# DCDC_Traco.net
KiCad netlist of a schematic drawn in Altium Designer
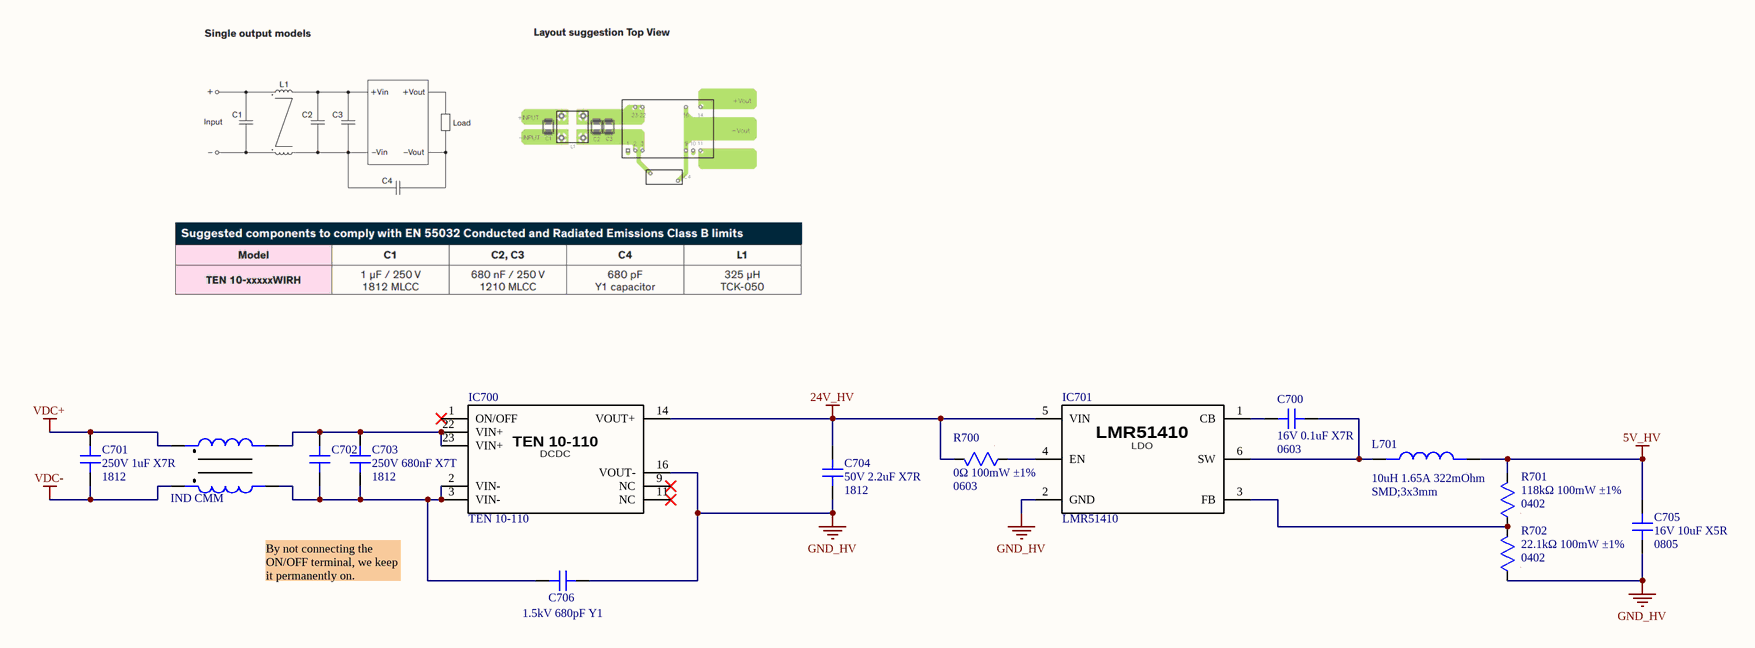
[diagram p0: DCDC_Traco.SchDoc]

(export (version "E")
  (design (tool "Eeschema 10.0.6"))
  (components
    (comp (ref "C700")
      (value "16V 0.1uF X7R")
      (footprint "CAP SMD 0603")
      (description "Condensadores de cerámica multicapa (MLCC- SMD/SMT) WCAP-CSGP 0.1uF 0603 10% 16V MLCC")
      (fields
        (field (name "PACKAGE") "0603")
        (field (name "MPN") "885012206046")
        (field (name "MANUFACTURER") "Wurth Elektronik")
      )
      (libsource (lib "eUSR_Database") (part "CAP non polarized"))
    )
    (comp (ref "C701")
      (value "250V 1uF X7R")
      (footprint "CAP SMD 1812")
      (description "Condensadores de cerámica multicapa (MLCC- SMD/SMT) 250V 1uF X7R 1812 10 %")
      (fields
        (field (name "PACKAGE") "1812")
        (field (name "MPN") "1812VC105KAT2A")
        (field (name "MANUFACTURER") "KYOCERA AVX")
      )
      (libsource (lib "eUSR_Database") (part "CAP non polarized"))
    )
    (comp (ref "C702")
      (value "CAP non polarized")
      (footprint "CAP SMD 1812")
      (description "Condensadores de cerámica multicapa (MLCC- SMD/SMT) 1812 250V 0.68uF X7T 20% T: 1.6mm")
      (fields (field (name "MPN") "C4532X7T2E684M160KA") (field (name "MANUFACTURER") "TDK"))
      (libsource (lib "eUSR_Database") (part "CAP non polarized"))
    )
    (comp (ref "C703")
      (value "250V 680nF X7T")
      (footprint "CAP SMD 1812")
      (description "Condensadores de cerámica multicapa (MLCC- SMD/SMT) 1812 250V 0.68uF X7T 20% T: 1.6mm")
      (fields
        (field (name "PACKAGE") "1812")
        (field (name "MPN") "C4532X7T2E684M160KA")
        (field (name "MANUFACTURER") "TDK")
      )
      (libsource (lib "eUSR_Database") (part "CAP non polarized"))
    )
    (comp (ref "C704")
      (value "50V 2.2uF X7R")
      (footprint "CAP SMD 1812")
      (description "Condensadores de cerámica multicapa (MLCC- SMD/SMT) WCAP-CSGP 2.2uF 1812 10% 50V MLCC")
      (fields
        (field (name "PACKAGE") "1812")
        (field (name "MPN") "885012210032")
        (field (name "MANUFACTURER") "Wurth Elektronik")
      )
      (libsource (lib "eUSR_Database") (part "CAP non polarized"))
    )
    (comp (ref "C705")
      (value "16V 10uF X5R")
      (footprint "CAP SMD 0805")
      (description "Condensadores de cerámica multicapa (MLCC- SMD/SMT) WCAP-CSGP 10uF 0805 20% 16V MLCC")
      (fields
        (field (name "PACKAGE") "0805")
        (field (name "MPN") "885012107014")
        (field (name "MANUFACTURER") "Wurth Elektronik")
      )
      (libsource (lib "eUSR_Database") (part "CAP non polarized"))
    )
    (comp (ref "C706")
      (value "1.5kV 680pF Y1")
      (footprint "CAP_15Px12.5H")
      (description "Condensadores de seguridad 500volts 680pF 20% LS=15mm")
      (fields (field (name "MPN") "P295BE681M500A") (field (name "MANUFACTURER") "KEMET"))
      (libsource (lib "eUSR_Database") (part "CAP non polarized"))
    )
    (comp (ref "IC700")
      (value "TEN 10-110")
      (footprint "TEN 10-110")
      (fields (field (name "MPN") "TEN 10-11015WIRH") (field (name "MANUFACTURER") "TRACO Power"))
      (libsource (lib "eUSR_Database") (part "TEN 10-110"))
    )
    (comp (ref "IC701")
      (value "LMR51410")
      (footprint "SOT-23-6")
      (description "Reguladores de tensión de conmutación SIMPLE SWITCHER 4V t o 42V 1A synchronou")
      (fields (field (name "MPN") "LMR51410YFDBVR") (field (name "MANUFACTURER") "Texas Instruments"))
      (libsource (lib "eUSR_Database") (part "LMR51410"))
    )
    (comp (ref "L700")
      (value "IND CMM")
      (footprint "IND_CMM_THT_11x11mm")
      (description "Cebadores / filtros de modo común Filter Component")
      (fields (field (name "MPN") "TCK-050") (field (name "MANUFACTURER") "TRACO Power"))
      (libsource (lib "eUSR_Database") (part "IND CMM"))
    )
    (comp (ref "L701")
      (value "10uH 1.65A 322mOhm")
      (footprint "IND SMD 3x3")
      (description "Inductores de potencia (SMD) WE-MAPI 10uH 1.2A DCR=322mOhms AEC-Q200")
      (fields
        (field (name "PACKAGE") "SMD;3x3mm")
        (field (name "MPN") "74438336100")
        (field (name "MANUFACTURER") "Wurth Elektronik")
      )
      (libsource (lib "eUSR_Database") (part "IND"))
    )
    (comp (ref "R700")
      (value "0Ω 100mW ±1%")
      (footprint "RES SMD 0603")
      (description "Resistores de película gruesa - SMD WRIS-RSKS <0.05 Ohms 0.1 W Jumper 0603 AEC-Q200")
      (fields
        (field (name "PACKAGE") "0603")
        (field (name "MPN") "5,60112116e+11")
        (field (name "MANUFACTURER") "Wurth Elektronik")
      )
      (libsource (lib "eUSR_Database") (part "RES"))
    )
    (comp (ref "R701")
      (value "118kΩ 100mW ±1%")
      (footprint "RES SMD 0402")
      (description "Resistores de película gruesa - SMD WRIS-RSKS 118 kOhms 1 % 0.1 W 0402 AEC-Q200")
      (fields
        (field (name "PACKAGE") "0402")
        (field (name "MPN") "560112110142")
        (field (name "MANUFACTURER") "Wurth Elektronik")
      )
      (libsource (lib "eUSR_Database") (part "RES"))
    )
    (comp (ref "R702")
      (value "22.1kΩ 100mW ±1%")
      (footprint "RES SMD 0402")
      (description "Resistores de película gruesa - SMD WRIS-RSKS 22.1 kOhms 1 % 0.1 W 0402 AEC-Q200")
      (fields
        (field (name "PACKAGE") "0402")
        (field (name "MPN") "560112110099")
        (field (name "MANUFACTURER") "Wurth Elektronik")
      )
      (libsource (lib "eUSR_Database") (part "RES"))
    )
  )
  (nets
    (net (code "1") (name "5V_HV") (class "Default")
      (node (ref "C705") (pin "1") (pinfunction "1_1") (pintype "passive"))
      (node (ref "L701") (pin "2") (pinfunction "2_2") (pintype "passive"))
      (node (ref "R701") (pin "2") (pinfunction "2_2") (pintype "passive"))
    )
    (net (code "2") (name "24V_HV") (class "Default")
      (node (ref "C704") (pin "1") (pinfunction "1_1") (pintype "passive"))
      (node (ref "IC700") (pin "14") (pinfunction "VOUT+_14") (pintype "passive"))
      (node (ref "IC701") (pin "5") (pinfunction "VIN_5") (pintype "passive"))
      (node (ref "R700") (pin "2") (pinfunction "2_2") (pintype "passive"))
    )
    (net (code "3") (name "GND_HV") (class "Default")
      (node (ref "C704") (pin "2") (pinfunction "2_2") (pintype "passive"))
      (node (ref "C705") (pin "2") (pinfunction "2_2") (pintype "passive"))
      (node (ref "C706") (pin "2") (pinfunction "2_2") (pintype "passive"))
      (node (ref "IC700") (pin "16") (pinfunction "VOUT-_16") (pintype "passive"))
      (node (ref "IC701") (pin "2") (pinfunction "GND_2") (pintype "passive"))
      (node (ref "R702") (pin "1") (pinfunction "1_1") (pintype "passive"))
    )
    (net (code "4") (name "Net-(C702-Pad1)") (class "Default")
      (node (ref "C702") (pin "1") (pinfunction "1_1") (pintype "passive"))
      (node (ref "C703") (pin "1") (pinfunction "1_1") (pintype "passive"))
      (node (ref "IC700") (pin "22") (pinfunction "VIN+_22") (pintype "passive"))
      (node (ref "IC700") (pin "23") (pinfunction "VIN+_23") (pintype "passive"))
      (node (ref "L700") (pin "2") (pinfunction "2_2") (pintype "passive"))
    )
    (net (code "5") (name "Net-(C702-Pad2)") (class "Default")
      (node (ref "C702") (pin "2") (pinfunction "2_2") (pintype "passive"))
      (node (ref "C703") (pin "2") (pinfunction "2_2") (pintype "passive"))
      (node (ref "C706") (pin "1") (pinfunction "1_1") (pintype "passive"))
      (node (ref "IC700") (pin "2") (pinfunction "VIN-_2") (pintype "passive"))
      (node (ref "IC700") (pin "3") (pinfunction "VIN-_3") (pintype "passive"))
      (node (ref "L700") (pin "3") (pinfunction "3_3") (pintype "passive"))
    )
    (net (code "6") (name "Net-(IC701-CB)") (class "Default")
      (node (ref "C700") (pin "1") (pinfunction "1_1") (pintype "passive"))
      (node (ref "IC701") (pin "1") (pinfunction "CB_1") (pintype "passive"))
    )
    (net (code "7") (name "Net-(IC701-EN)") (class "Default")
      (node (ref "IC701") (pin "4") (pinfunction "EN_4") (pintype "passive"))
      (node (ref "R700") (pin "1") (pinfunction "1_1") (pintype "passive"))
    )
    (net (code "8") (name "Net-(IC701-FB)") (class "Default")
      (node (ref "IC701") (pin "3") (pinfunction "FB_3") (pintype "passive"))
      (node (ref "R701") (pin "1") (pinfunction "1_1") (pintype "passive"))
      (node (ref "R702") (pin "2") (pinfunction "2_2") (pintype "passive"))
    )
    (net (code "9") (name "Net-(IC701-SW)") (class "Default")
      (node (ref "C700") (pin "2") (pinfunction "2_2") (pintype "passive"))
      (node (ref "IC701") (pin "6") (pinfunction "SW_6") (pintype "passive"))
      (node (ref "L701") (pin "1") (pinfunction "1_1") (pintype "passive"))
    )
    (net (code "10") (name "VDC+") (class "Default")
      (node (ref "C701") (pin "1") (pinfunction "1_1") (pintype "passive"))
      (node (ref "L700") (pin "1") (pinfunction "1_1") (pintype "passive"))
    )
    (net (code "11") (name "VDC-") (class "Default")
      (node (ref "C701") (pin "2") (pinfunction "2_2") (pintype "passive"))
      (node (ref "L700") (pin "4") (pinfunction "4_4") (pintype "passive"))
    )
    (net (code "12") (name "unconnected-(IC700-NC-Pad9)") (class "Default")
      (node (ref "IC700") (pin "9") (pinfunction "NC_9") (pintype "passive+no_connect"))
    )
    (net (code "13") (name "unconnected-(IC700-NC-Pad11)") (class "Default")
      (node (ref "IC700") (pin "11") (pinfunction "NC_11") (pintype "passive+no_connect"))
    )
    (net (code "14") (name "unconnected-(IC700-ON{slash}OFF-Pad1)") (class "Default")
      (node (ref "IC700") (pin "1") (pinfunction "ON/OFF_1") (pintype "passive+no_connect"))
    )
  )
)
